# EEPROM.net
KiCad netlist of a schematic drawn in Altium Designer
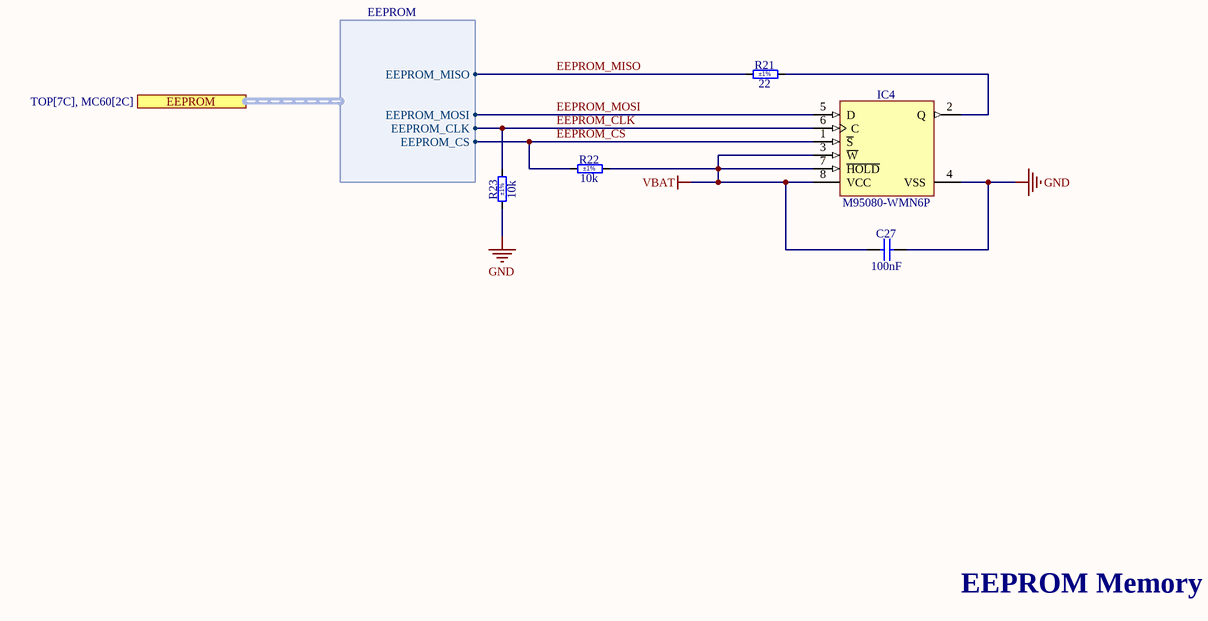
[diagram p0: EEPROM.SchDoc]

(export (version "E")
  (design (tool "Eeschema 10.0.6"))
  (components
    (comp (ref "C27")
      (value "100nF")
      (footprint "CAPC1608X87N")
      (description "Non-polarised capacitor")
      (fields
        (field (name "PART NUMBER") "CC0603_100NF_50V_10%_X7R")
        (field (name "VOLTAGE") "50V")
        (field (name "AUTHOR") "CERN DEM JLC")
      )
      (libsource (lib "Capacitors") (part "Capacitor - non polarized"))
    )
    (comp (ref "IC4")
      (value "M95080-WMN6P")
      (footprint "SOIC127P600X175-8N")
      (description "2.5 to 5.5 V, 8Kb (1024x8) Serial SPI Bus EEPROM with High-Speed Clock")
      (fields (field (name "MANUFACTURER") "ST MICROELECTRONICS") (field (name "AUTHOR") "CERN DEM JLC"))
      (libsource (lib "ICs And Semiconductors") (part "M95080"))
    )
    (comp (ref "R21")
      (value "22")
      (footprint "RESC1608X55N")
      (description "Resistor - 1%")
      (fields
        (field (name "TOLERANCE") "±1%")
        (field (name "PART NUMBER") "R0603_22R_1%_0.1W_100PPM")
        (field (name "POWER") "0.1W")
        (field (name "AUTHOR") "CERN DEM JLC")
      )
      (libsource (lib "Resistors") (part "Resistor - 1%"))
    )
    (comp (ref "R22")
      (value "10k")
      (footprint "RESC1608X55N")
      (description "Resistor - 1%")
      (fields
        (field (name "TOLERANCE") "±1%")
        (field (name "PART NUMBER") "R0603_10K_1%_0.1W_100PPM")
        (field (name "POWER") "0.1W")
        (field (name "AUTHOR") "CERN DEM JLC")
      )
      (libsource (lib "Resistors") (part "Resistor - 1%"))
    )
    (comp (ref "R23")
      (value "10k")
      (footprint "RESC1608X55N")
      (description "Resistor - 1%")
      (fields
        (field (name "TOLERANCE") "±1%")
        (field (name "PART NUMBER") "R0603_10K_1%_0.1W_100PPM")
        (field (name "POWER") "0.1W")
        (field (name "AUTHOR") "CERN DEM JLC")
      )
      (libsource (lib "Resistors") (part "Resistor - 1%"))
    )
  )
  (nets
    (net (code "2") (name "/EEPROM_CLK") (class "Default")
      (node (ref "IC4") (pin "6") (pinfunction "C_6") (pintype "input"))
      (node (ref "R23") (pin "2") (pinfunction "2_2") (pintype "passive"))
    )
    (net (code "3") (name "/EEPROM_CS") (class "Default")
      (node (ref "IC4") (pin "1") (pinfunction "~{S}_1") (pintype "input"))
      (node (ref "R22") (pin "1") (pinfunction "1_1") (pintype "passive"))
    )
    (net (code "4") (name "/EEPROM_MISO") (class "Default")
      (node (ref "R21") (pin "1") (pinfunction "1_1") (pintype "passive"))
    )
    (net (code "5") (name "/EEPROM_MOSI") (class "Default")
      (node (ref "IC4") (pin "5") (pinfunction "D_5") (pintype "input"))
    )
    (net (code "7") (name "GND") (class "Default")
      (node (ref "C27") (pin "2") (pinfunction "2_2") (pintype "passive"))
      (node (ref "IC4") (pin "4") (pinfunction "VSS_4") (pintype "power_in"))
      (node (ref "R23") (pin "1") (pinfunction "1_1") (pintype "passive"))
    )
    (net (code "8") (name "Net-(IC4-Q)") (class "Default")
      (node (ref "IC4") (pin "2") (pinfunction "Q_2") (pintype "output"))
      (node (ref "R21") (pin "2") (pinfunction "2_2") (pintype "passive"))
    )
    (net (code "9") (name "VBAT") (class "Default")
      (node (ref "C27") (pin "1") (pinfunction "1_1") (pintype "passive"))
      (node (ref "IC4") (pin "3") (pinfunction "~{W}_3") (pintype "input"))
      (node (ref "IC4") (pin "7") (pinfunction "~{HOLD}_7") (pintype "input"))
      (node (ref "IC4") (pin "8") (pinfunction "VCC_8") (pintype "power_in"))
      (node (ref "R22") (pin "2") (pinfunction "2_2") (pintype "passive"))
    )
  )
)
